# Schematic.net
KiCad netlist of a schematic drawn in EAGLE
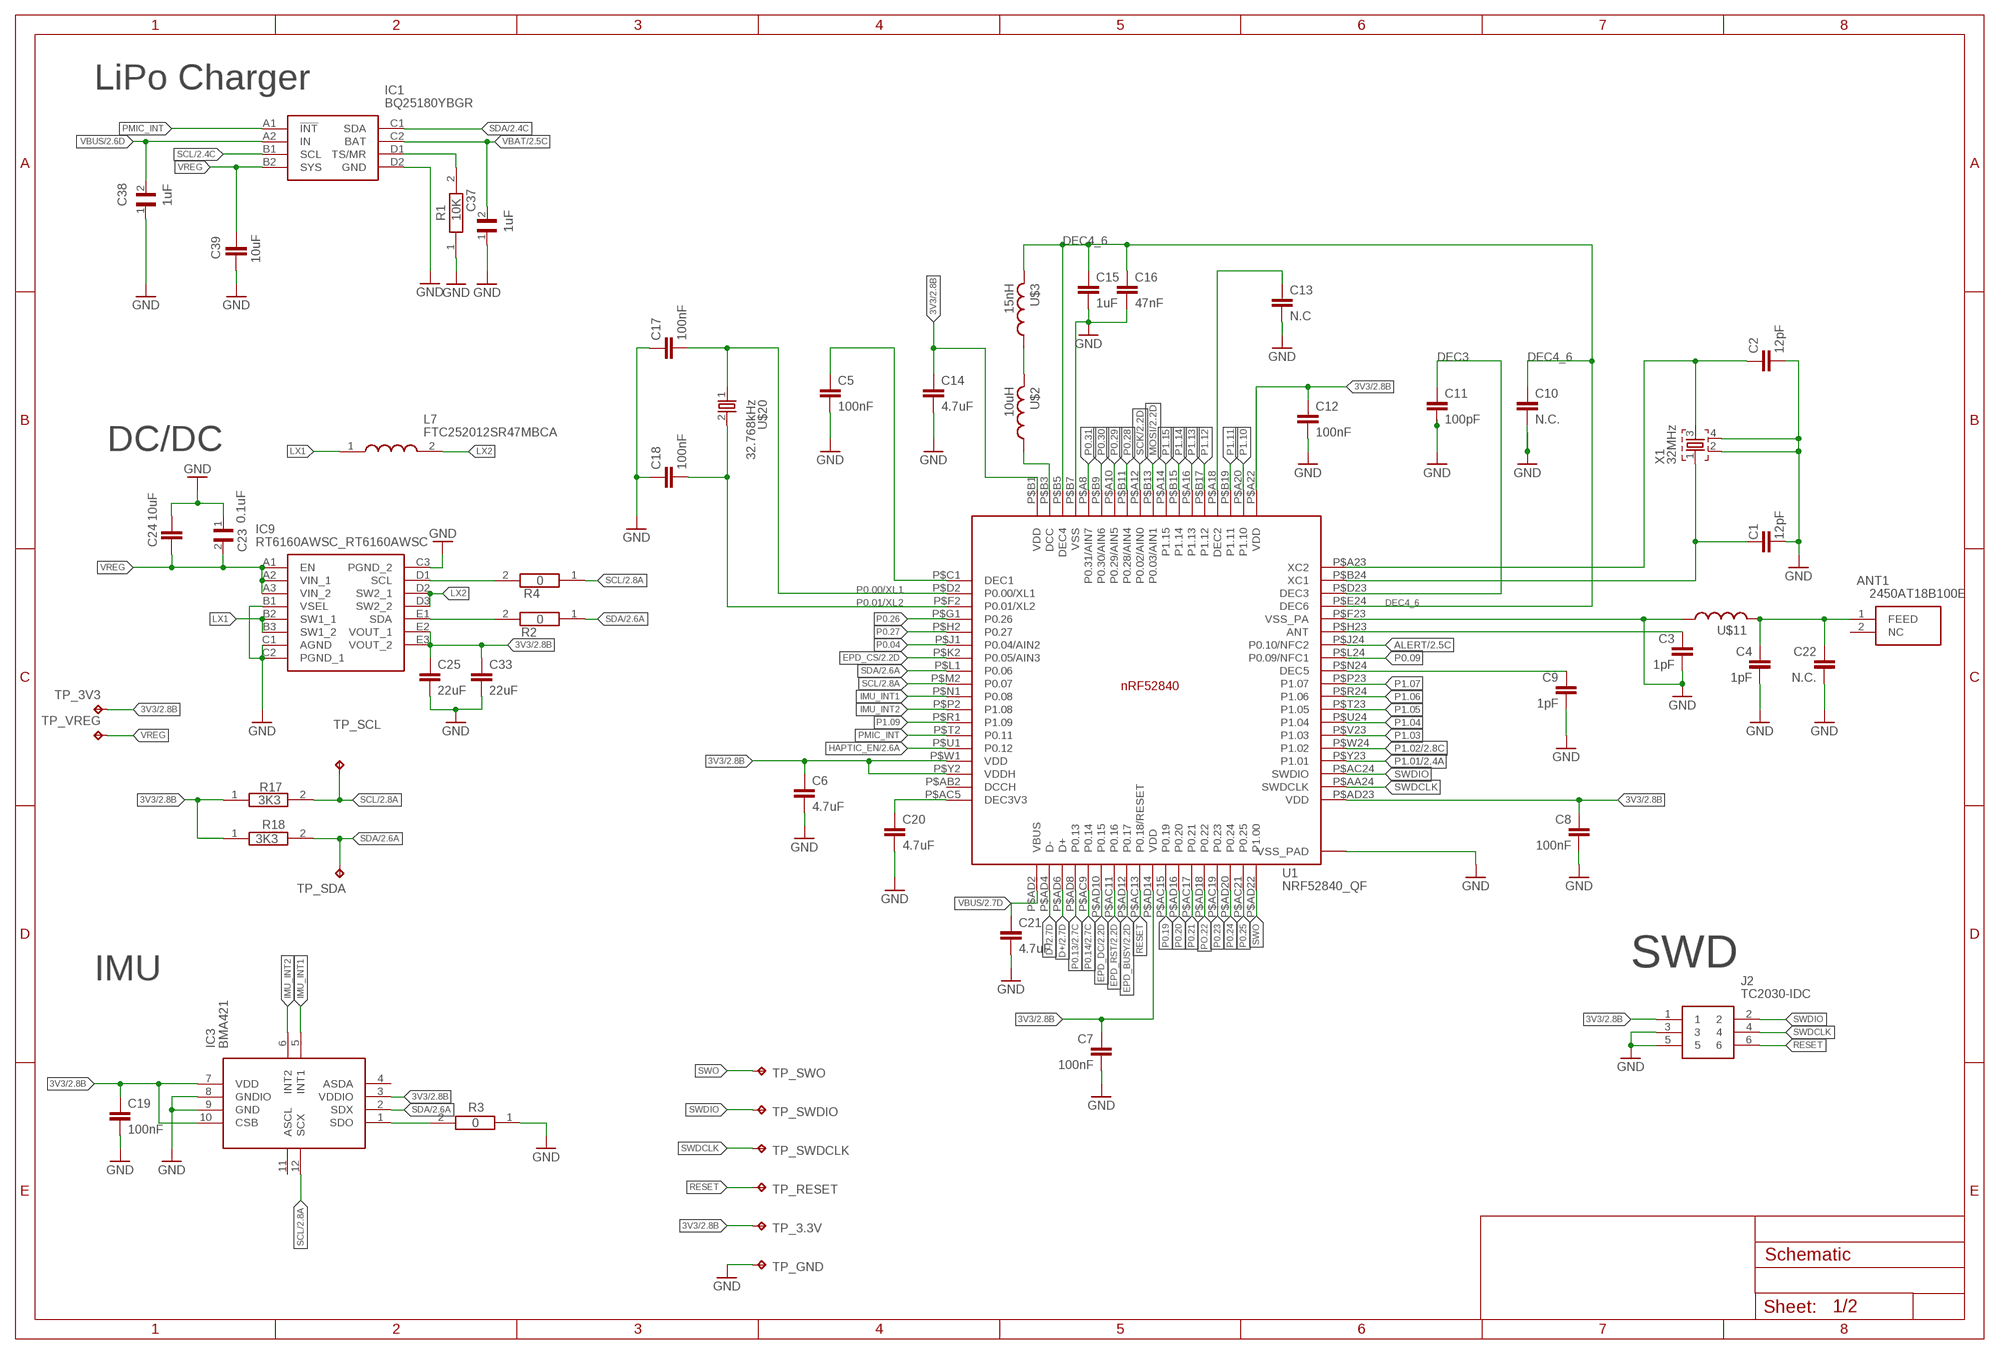
[diagram p0: schematic, sheet 1]
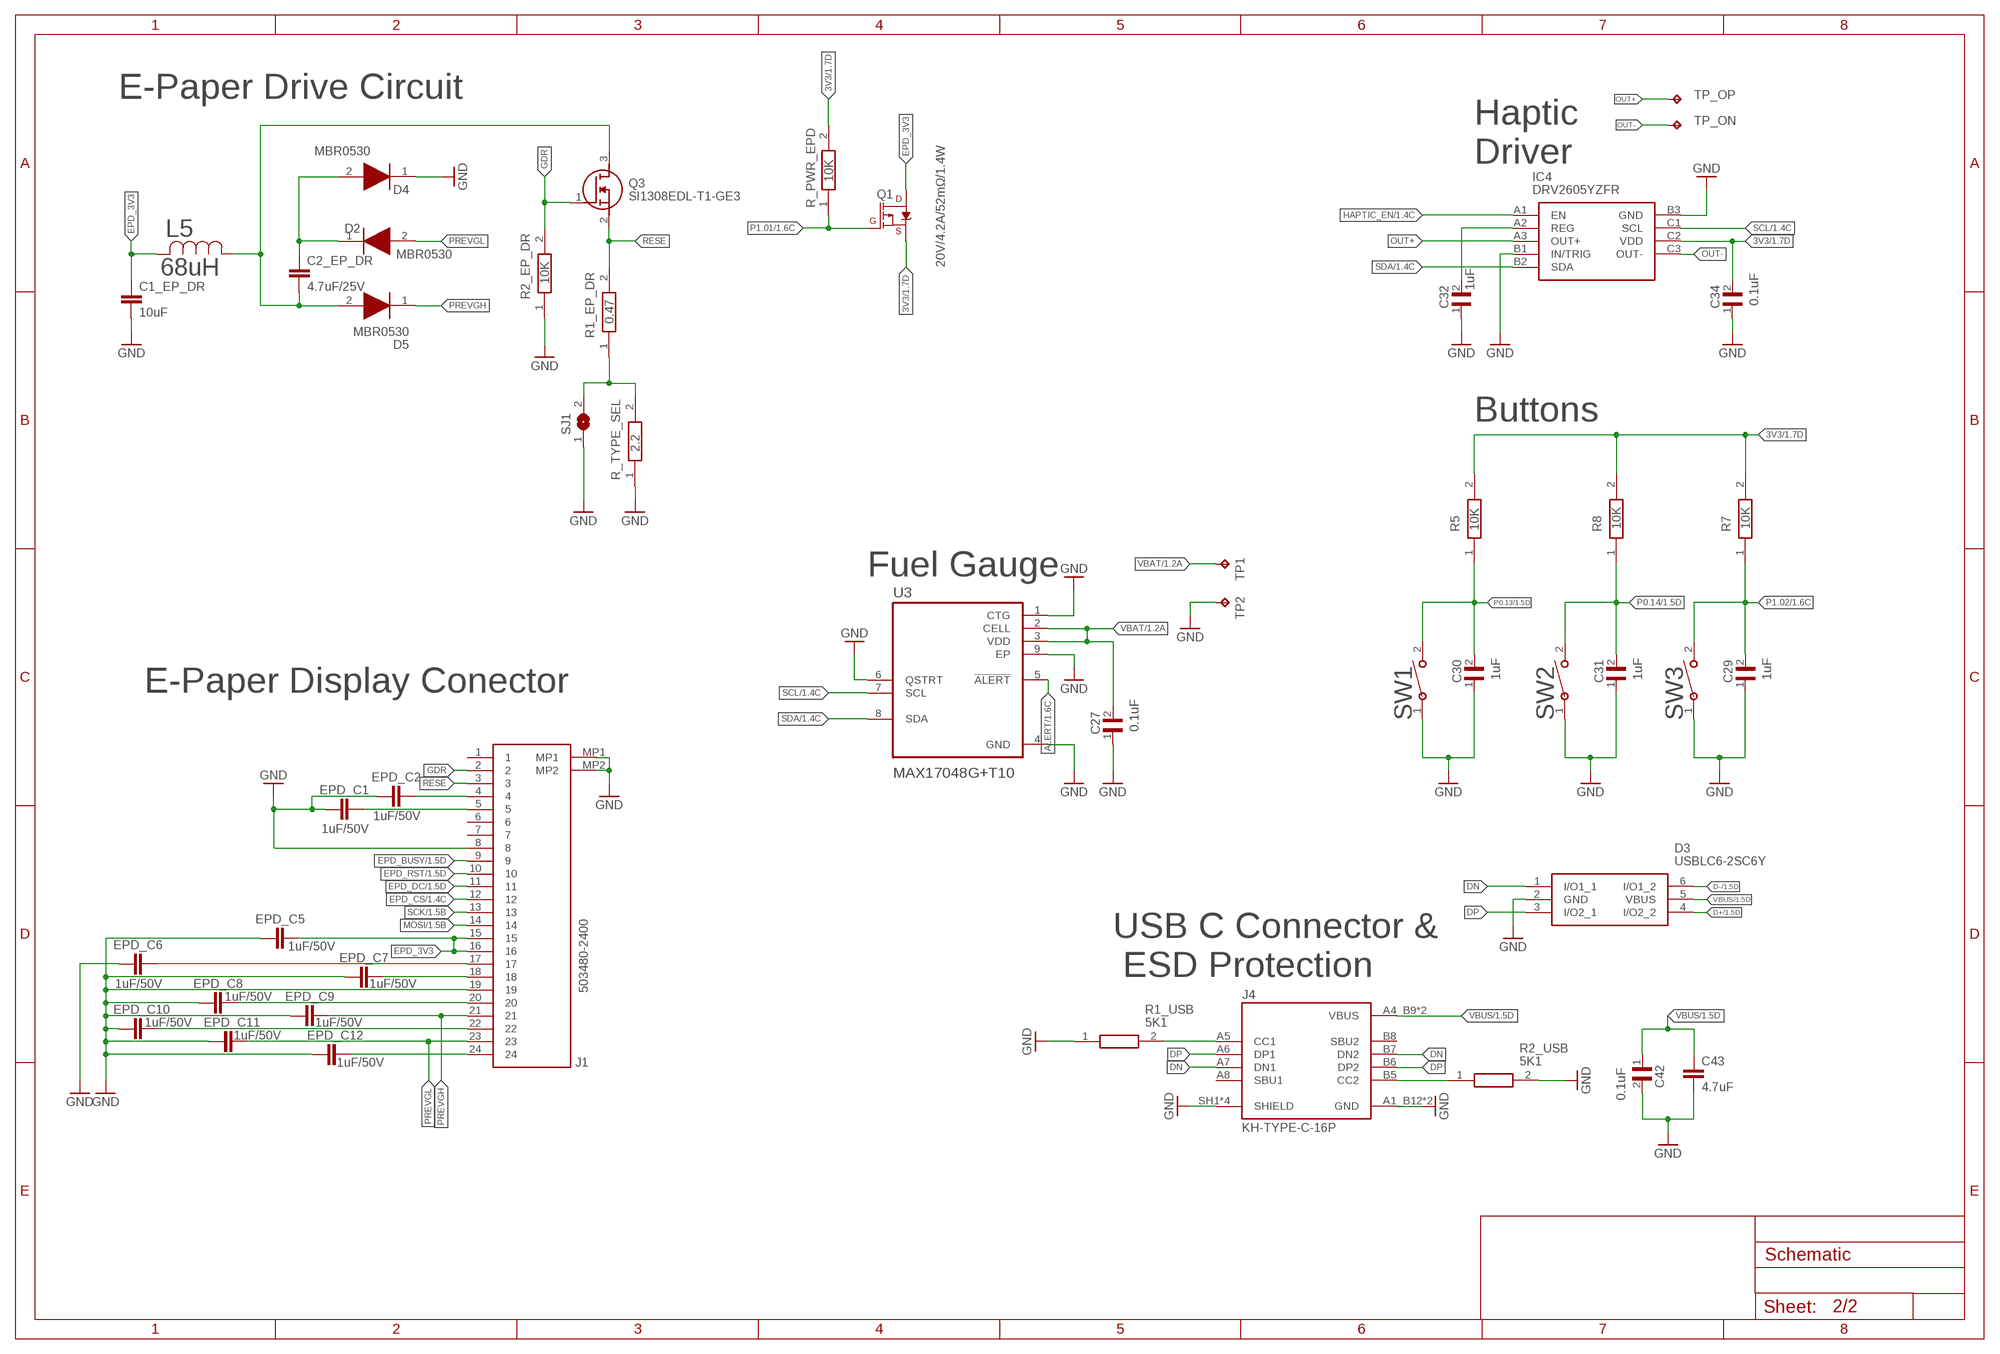
[diagram p1: schematic, sheet 2]

(export (version "E")
  (design (tool "Eeschema 10.0.6"))
  (components
    (comp (ref "C1_EP_DR")
      (value "10uF")
      (footprint "eagle-import:PERFECT_0402_0402")
      (libsource (lib "eagle-import") (part "PERFECT_0402_CAP_0402"))
    )
    (comp (ref "C2_EP_DR")
      (value "4.7uF/25V")
      (footprint "eagle-import:PERFECT_0402_0402")
      (libsource (lib "eagle-import") (part "PERFECT_0402_CAP_0402"))
    )
    (comp (ref "C27")
      (value "0.1uF")
      (footprint "eagle-import:GRM011R60J152KE01L_2_CAPC0201X13N")
      (fields (field (name "MF") "Murata") (field (name "MP") "GRM011R60J152KE01L"))
      (libsource (lib "eagle-import") (part "GRM011R60J152KE01L_2_GRM011R60J152KE01L"))
    )
    (comp (ref "C29")
      (value "1uF")
      (footprint "eagle-import:GRM011R60J152KE01L_2_CAPC0201X13N")
      (fields (field (name "MF") "Murata") (field (name "MP") "GRM011R60J152KE01L"))
      (libsource (lib "eagle-import") (part "GRM011R60J152KE01L_2_GRM011R60J152KE01L"))
    )
    (comp (ref "C30")
      (value "1uF")
      (footprint "eagle-import:GRM011R60J152KE01L_2_CAPC0201X13N")
      (fields (field (name "MF") "Murata") (field (name "MP") "GRM011R60J152KE01L"))
      (libsource (lib "eagle-import") (part "GRM011R60J152KE01L_2_GRM011R60J152KE01L"))
    )
    (comp (ref "C31")
      (value "1uF")
      (footprint "eagle-import:GRM011R60J152KE01L_2_CAPC0201X13N")
      (fields (field (name "MF") "Murata") (field (name "MP") "GRM011R60J152KE01L"))
      (libsource (lib "eagle-import") (part "GRM011R60J152KE01L_2_GRM011R60J152KE01L"))
    )
    (comp (ref "C32")
      (value "1uF")
      (footprint "eagle-import:GRM011R60J152KE01L_2_CAPC0201X13N")
      (fields (field (name "MF") "Murata") (field (name "MP") "GRM011R60J152KE01L"))
      (libsource (lib "eagle-import") (part "GRM011R60J152KE01L_2_GRM011R60J152KE01L"))
    )
    (comp (ref "C34")
      (value "0.1uF")
      (footprint "eagle-import:GRM011R60J152KE01L_2_CAPC0201X13N")
      (fields (field (name "MF") "Murata") (field (name "MP") "GRM011R60J152KE01L"))
      (libsource (lib "eagle-import") (part "GRM011R60J152KE01L_2_GRM011R60J152KE01L"))
    )
    (comp (ref "C42")
      (value "0.1uF")
      (footprint "eagle-import:GRM011R60J152KE01L_2_CAPC0201X13N")
      (fields (field (name "MF") "Murata") (field (name "MP") "GRM011R60J152KE01L"))
      (libsource (lib "eagle-import") (part "GRM011R60J152KE01L_2_GRM011R60J152KE01L"))
    )
    (comp (ref "C43")
      (value "4.7uF")
      (footprint "eagle-import:PERFECT_0402_0402")
      (libsource (lib "eagle-import") (part "PERFECT_0402_CAP_0402"))
    )
    (comp (ref "D2")
      (value "MBR0530")
      (footprint "eagle-import:ESP32_C6_LIBRARY_5_SOD3716X135N")
      (fields (field (name "MF") "ON Semiconductor"))
      (libsource (lib "eagle-import") (part "ESP32_C6_LIBRARY_5_MBR0530"))
    )
    (comp (ref "D3")
      (value "USBLC6-2SC6Y")
      (footprint "eagle-import:ESP32_C6_LIBRARY_3_SOT95P280X145-6N")
      (fields (field (name "MF") "STMicroelectronics"))
      (libsource (lib "eagle-import") (part "ESP32_C6_LIBRARY_3_USBLC6-2SC6Y"))
    )
    (comp (ref "D4")
      (value "MBR0530")
      (footprint "eagle-import:ESP32_C6_LIBRARY_5_SOD3716X135N")
      (fields (field (name "MF") "ON Semiconductor"))
      (libsource (lib "eagle-import") (part "ESP32_C6_LIBRARY_5_MBR0530"))
    )
    (comp (ref "D5")
      (value "MBR0530")
      (footprint "eagle-import:ESP32_C6_LIBRARY_5_SOD3716X135N")
      (fields (field (name "MF") "ON Semiconductor"))
      (libsource (lib "eagle-import") (part "ESP32_C6_LIBRARY_5_MBR0530"))
    )
    (comp (ref "EPD_C1")
      (value "1uF/50V")
      (footprint "eagle-import:PERFECT_0402_0402")
      (libsource (lib "eagle-import") (part "PERFECT_0402_CAP_0402"))
    )
    (comp (ref "EPD_C2")
      (value "1uF/50V")
      (footprint "eagle-import:PERFECT_0402_0402")
      (libsource (lib "eagle-import") (part "PERFECT_0402_CAP_0402"))
    )
    (comp (ref "EPD_C5")
      (value "1uF/50V")
      (footprint "eagle-import:PERFECT_0402_0402")
      (libsource (lib "eagle-import") (part "PERFECT_0402_CAP_0402"))
    )
    (comp (ref "EPD_C6")
      (value "1uF/50V")
      (footprint "eagle-import:PERFECT_0402_0402")
      (libsource (lib "eagle-import") (part "PERFECT_0402_CAP_0402"))
    )
    (comp (ref "EPD_C7")
      (value "1uF/50V")
      (footprint "eagle-import:PERFECT_0402_0402")
      (libsource (lib "eagle-import") (part "PERFECT_0402_CAP_0402"))
    )
    (comp (ref "EPD_C8")
      (value "1uF/50V")
      (footprint "eagle-import:PERFECT_0402_0402")
      (libsource (lib "eagle-import") (part "PERFECT_0402_CAP_0402"))
    )
    (comp (ref "EPD_C9")
      (value "1uF/50V")
      (footprint "eagle-import:PERFECT_0402_0402")
      (libsource (lib "eagle-import") (part "PERFECT_0402_CAP_0402"))
    )
    (comp (ref "EPD_C10")
      (value "1uF/50V")
      (footprint "eagle-import:PERFECT_0402_0402")
      (libsource (lib "eagle-import") (part "PERFECT_0402_CAP_0402"))
    )
    (comp (ref "EPD_C11")
      (value "1uF/50V")
      (footprint "eagle-import:PERFECT_0402_0402")
      (libsource (lib "eagle-import") (part "PERFECT_0402_CAP_0402"))
    )
    (comp (ref "EPD_C12")
      (value "1uF/50V")
      (footprint "eagle-import:PERFECT_0402_0402")
      (libsource (lib "eagle-import") (part "PERFECT_0402_CAP_0402"))
    )
    (comp (ref "IC4")
      (value "DRV2605YZFR")
      (footprint "eagle-import:DRV2605YZFR_BGA9C50P3X3_144X144X62")
      (libsource (lib "eagle-import") (part "DRV2605YZFR_DRV2605YZFR"))
    )
    (comp (ref "J1")
      (value "503480-2400")
      (footprint "eagle-import:503480-2400_5034802400")
      (fields (field (name "MOUSER_PART_NUMBER") "538-503480-2400"))
      (libsource (lib "eagle-import") (part "503480-2400_503480-2400"))
    )
    (comp (ref "J4")
      (value "KH-TYPE-C-16P")
      (footprint "eagle-import:KH-TYPE-C-16P_KINGHELM_KH-TYPE-C-16P")
      (fields (field (name "MF") "kinghelm"))
      (libsource (lib "eagle-import") (part "KH-TYPE-C-16P_KH-TYPE-C-16P"))
    )
    (comp (ref "L5")
      (value "68uH")
      (footprint "eagle-import:ESP32_C6_LIBRARY_2_IND_4828-WE-TPC_WRE")
      (fields
        (field (name "MANUFACTURER_PART_NUMBER") "744043680")
        (field (name "COPYRIGHT") "Copyright (C) 2024 Ultra Librarian. All rights reserved.")
      )
      (libsource (lib "eagle-import") (part "ESP32_C6_LIBRARY_2_744043680IND_4828-WE-TPC_WRE"))
    )
    (comp (ref "Q1")
      (value "20V/4.2A/52mΩ/1.4W")
      (footprint "eagle-import:ESP32_C6_LIBRARY_4_ESP32_C6_LIBRARY_4_ESP32_C6_LIBRARY_4_ESP32_C6_LIBRARY_4_ESP32_WROVER_SPARKFUN-DISCRETESEMI_SOT23-3")
      (libsource (lib "eagle-import") (part "ESP32_C6_LIBRARY_4_ESP32_WROVER_SPARKFUN-DISCRETESEMI_MOSFET_PCH-DMG2305UX-7"))
    )
    (comp (ref "Q3")
      (value "SI1308EDL-T1-GE3")
      (footprint "eagle-import:ESP32_C6_LIBRARY_6_SOT65P210X110-3N")
      (fields (field (name "MF") "Vishay Siliconix"))
      (libsource (lib "eagle-import") (part "ESP32_C6_LIBRARY_6_SI1308EDL-T1-GE3"))
    )
    (comp (ref "R1_EP_DR")
      (value "0.47")
      (footprint "eagle-import:CPF0201D7K68C1_0201")
      (libsource (lib "eagle-import") (part "CPF0201D7K68C1_CPF0201D7K68C1"))
    )
    (comp (ref "R1_USB")
      (value "5K1")
      (footprint "eagle-import:CPF0201D7K68C1_0201")
      (libsource (lib "eagle-import") (part "CPF0201D7K68C1_CPF0201D7K68C1"))
    )
    (comp (ref "R2_EP_DR")
      (value "10K")
      (footprint "eagle-import:CPF0201D7K68C1_0201")
      (libsource (lib "eagle-import") (part "CPF0201D7K68C1_CPF0201D7K68C1"))
    )
    (comp (ref "R2_USB")
      (value "5K1")
      (footprint "eagle-import:CPF0201D7K68C1_0201")
      (libsource (lib "eagle-import") (part "CPF0201D7K68C1_CPF0201D7K68C1"))
    )
    (comp (ref "R5")
      (value "10K")
      (footprint "eagle-import:CPF0201D7K68C1_0201")
      (libsource (lib "eagle-import") (part "CPF0201D7K68C1_CPF0201D7K68C1"))
    )
    (comp (ref "R7")
      (value "10K")
      (footprint "eagle-import:CPF0201D7K68C1_0201")
      (libsource (lib "eagle-import") (part "CPF0201D7K68C1_CPF0201D7K68C1"))
    )
    (comp (ref "R8")
      (value "10K")
      (footprint "eagle-import:CPF0201D7K68C1_0201")
      (libsource (lib "eagle-import") (part "CPF0201D7K68C1_CPF0201D7K68C1"))
    )
    (comp (ref "R_PWR_EPD")
      (value "10K")
      (footprint "eagle-import:CPF0201D7K68C1_0201")
      (libsource (lib "eagle-import") (part "CPF0201D7K68C1_CPF0201D7K68C1"))
    )
    (comp (ref "R_TYPE_SEL")
      (value "2.2")
      (footprint "eagle-import:CPF0201D7K68C1_0201")
      (libsource (lib "eagle-import") (part "CPF0201D7K68C1_CPF0201D7K68C1"))
    )
    (comp (ref "SJ1")
      (value "ESP32_C6_LIBRARY_7_JUMPER_SJ")
      (footprint "eagle-import:ESP32_C6_LIBRARY_7_JUMPER_SJ")
      (libsource (lib "eagle-import") (part "ESP32_C6_LIBRARY_7_JUMPER_SJ"))
    )
    (comp (ref "SW1")
      (value "2025-10-22_07-23-44_LIBRARY_EVP-AKE31ASW_EVP-AKE31A_PAN")
      (footprint "eagle-import:2025-10-22_07-23-44_LIBRARY_SW_EVP-AKE31A_PAN")
      (fields
        (field (name "MANUFACTURER_PART_NUMBER") "EVP-AKE31A")
        (field (name "COPYRIGHT") "Copyright (C) 2025 Ultra Librarian. All rights reserved.")
      )
      (libsource (lib "eagle-import") (part "2025-10-22_07-23-44_LIBRARY_EVP-AKE31ASW_EVP-AKE31A_PAN"))
    )
    (comp (ref "SW2")
      (value "2025-10-22_07-23-44_LIBRARY_EVP-AKE31ASW_EVP-AKE31A_PAN")
      (footprint "eagle-import:2025-10-22_07-23-44_LIBRARY_SW_EVP-AKE31A_PAN")
      (fields
        (field (name "MANUFACTURER_PART_NUMBER") "EVP-AKE31A")
        (field (name "COPYRIGHT") "Copyright (C) 2025 Ultra Librarian. All rights reserved.")
      )
      (libsource (lib "eagle-import") (part "2025-10-22_07-23-44_LIBRARY_EVP-AKE31ASW_EVP-AKE31A_PAN"))
    )
    (comp (ref "SW3")
      (value "2025-10-22_07-23-44_LIBRARY_EVP-AKE31ASW_EVP-AKE31A_PAN")
      (footprint "eagle-import:2025-10-22_07-23-44_LIBRARY_SW_EVP-AKE31A_PAN")
      (fields
        (field (name "MANUFACTURER_PART_NUMBER") "EVP-AKE31A")
        (field (name "COPYRIGHT") "Copyright (C) 2025 Ultra Librarian. All rights reserved.")
      )
      (libsource (lib "eagle-import") (part "2025-10-22_07-23-44_LIBRARY_EVP-AKE31ASW_EVP-AKE31A_PAN"))
    )
    (comp (ref "TP1")
      (value "HECTOR_WATCH_1_TPTP20R")
      (footprint "eagle-import:HECTOR_WATCH_1_TP20R")
      (libsource (lib "eagle-import") (part "HECTOR_WATCH_1_TPTP20R"))
    )
    (comp (ref "TP2")
      (value "HECTOR_WATCH_1_TPTP20R")
      (footprint "eagle-import:HECTOR_WATCH_1_TP20R")
      (libsource (lib "eagle-import") (part "HECTOR_WATCH_1_TPTP20R"))
    )
    (comp (ref "TP_ON")
      (value "HECTOR_WATCH_1_TPTP20R")
      (footprint "eagle-import:HECTOR_WATCH_1_TP20R")
      (libsource (lib "eagle-import") (part "HECTOR_WATCH_1_TPTP20R"))
    )
    (comp (ref "TP_OP")
      (value "HECTOR_WATCH_1_TPTP20R")
      (footprint "eagle-import:HECTOR_WATCH_1_TP20R")
      (libsource (lib "eagle-import") (part "HECTOR_WATCH_1_TPTP20R"))
    )
    (comp (ref "U3")
      (value "MAX17048G+T10")
      (footprint "eagle-import:ESP32_C6_LIBRARY_SON50P200X200X80-9N")
      (fields (field (name "MF") "Analog Devices"))
      (libsource (lib "eagle-import") (part "ESP32_C6_LIBRARY_MAX17048G+T10"))
    )
    (comp (ref "ANT1")
      (value "2450AT18B100E")
      (footprint "eagle-import:2450AT18B100E_ANTC3216X140N")
      (fields (field (name "MOUSER_PART_NUMBER") "609-2450AT18B100E"))
      (libsource (lib "eagle-import") (part "2450AT18B100E_2450AT18B100E"))
    )
    (comp (ref "C1")
      (value "12pF")
      (footprint "eagle-import:NORDIC_NRF_3_RESC0201_L")
      (libsource (lib "eagle-import") (part "NORDIC_NRF_3_CAPACITOR_0201_L"))
    )
    (comp (ref "C2")
      (value "12pF")
      (footprint "eagle-import:NORDIC_NRF_3_RESC0201_L")
      (libsource (lib "eagle-import") (part "NORDIC_NRF_3_CAPACITOR_0201_L"))
    )
    (comp (ref "C3")
      (value "1pF")
      (footprint "eagle-import:NORDIC_NRF_3_RESC0201_L")
      (libsource (lib "eagle-import") (part "NORDIC_NRF_3_CAPACITOR_0201_L"))
    )
    (comp (ref "C4")
      (value "1pF")
      (footprint "eagle-import:NORDIC_NRF_3_RESC0201_L")
      (libsource (lib "eagle-import") (part "NORDIC_NRF_3_CAPACITOR_0201_L"))
    )
    (comp (ref "C5")
      (value "100nF")
      (footprint "eagle-import:NORDIC_NRF_3_RESC0201_L")
      (libsource (lib "eagle-import") (part "NORDIC_NRF_3_CAPACITOR_0201_L"))
    )
    (comp (ref "C6")
      (value "4.7uF")
      (footprint "eagle-import:PERFECT_0402_0402")
      (libsource (lib "eagle-import") (part "PERFECT_0402_CAP_0402"))
    )
    (comp (ref "C7")
      (value "100nF")
      (footprint "eagle-import:NORDIC_NRF_3_RESC0201_L")
      (libsource (lib "eagle-import") (part "NORDIC_NRF_3_CAPACITOR_0201_L"))
    )
    (comp (ref "C8")
      (value "100nF")
      (footprint "eagle-import:NORDIC_NRF_3_RESC0201_L")
      (libsource (lib "eagle-import") (part "NORDIC_NRF_3_CAPACITOR_0201_L"))
    )
    (comp (ref "C9")
      (value "1pF")
      (footprint "eagle-import:NORDIC_NRF_3_RESC0201_L")
      (libsource (lib "eagle-import") (part "NORDIC_NRF_3_CAPACITOR_0201_L"))
    )
    (comp (ref "C10")
      (value "N.C.")
      (footprint "eagle-import:NORDIC_NRF_3_RESC0201_L")
      (libsource (lib "eagle-import") (part "NORDIC_NRF_3_CAPACITOR_0201_L"))
    )
    (comp (ref "C11")
      (value "100pF")
      (footprint "eagle-import:NORDIC_NRF_3_RESC0201_L")
      (libsource (lib "eagle-import") (part "NORDIC_NRF_3_CAPACITOR_0201_L"))
    )
    (comp (ref "C12")
      (value "100nF")
      (footprint "eagle-import:NORDIC_NRF_3_RESC0201_L")
      (libsource (lib "eagle-import") (part "NORDIC_NRF_3_CAPACITOR_0201_L"))
    )
    (comp (ref "C13")
      (value "N.C")
      (footprint "eagle-import:NORDIC_NRF_3_RESC0201_L")
      (libsource (lib "eagle-import") (part "NORDIC_NRF_3_CAPACITOR_0201_L"))
    )
    (comp (ref "C14")
      (value "4.7uF")
      (footprint "eagle-import:PERFECT_0402_0402")
      (libsource (lib "eagle-import") (part "PERFECT_0402_CAP_0402"))
    )
    (comp (ref "C15")
      (value "1uF")
      (footprint "eagle-import:PERFECT_0402_0402")
      (libsource (lib "eagle-import") (part "PERFECT_0402_CAP_0402"))
    )
    (comp (ref "C16")
      (value "47nF")
      (footprint "eagle-import:NORDIC_NRF_3_RESC0201_L")
      (libsource (lib "eagle-import") (part "NORDIC_NRF_3_CAPACITOR_0201_L"))
    )
    (comp (ref "C17")
      (value "100nF")
      (footprint "eagle-import:NORDIC_NRF_3_RESC0201_L")
      (libsource (lib "eagle-import") (part "NORDIC_NRF_3_CAPACITOR_0201_L"))
    )
    (comp (ref "C18")
      (value "100nF")
      (footprint "eagle-import:NORDIC_NRF_3_RESC0201_L")
      (libsource (lib "eagle-import") (part "NORDIC_NRF_3_CAPACITOR_0201_L"))
    )
    (comp (ref "C19")
      (value "100nF")
      (footprint "eagle-import:NORDIC_NRF_3_RESC0201_L")
      (libsource (lib "eagle-import") (part "NORDIC_NRF_3_CAPACITOR_0201_L"))
    )
    (comp (ref "C20")
      (value "4.7uF")
      (footprint "eagle-import:PERFECT_0402_0402")
      (libsource (lib "eagle-import") (part "PERFECT_0402_CAP_0402"))
    )
    (comp (ref "C21")
      (value "4.7uF")
      (footprint "eagle-import:PERFECT_0402_0402")
      (libsource (lib "eagle-import") (part "PERFECT_0402_CAP_0402"))
    )
    (comp (ref "C22")
      (value "N.C.")
      (footprint "eagle-import:NORDIC_NRF_3_RESC0201_L")
      (libsource (lib "eagle-import") (part "NORDIC_NRF_3_CAPACITOR_0201_L"))
    )
    (comp (ref "C23")
      (value "0.1uF")
      (footprint "eagle-import:GRM011R60J152KE01L_2_CAPC0201X13N")
      (fields (field (name "MF") "Murata") (field (name "MP") "GRM011R60J152KE01L"))
      (libsource (lib "eagle-import") (part "GRM011R60J152KE01L_2_GRM011R60J152KE01L"))
    )
    (comp (ref "C24")
      (value "10uF")
      (footprint "eagle-import:PERFECT_0402_0402")
      (libsource (lib "eagle-import") (part "PERFECT_0402_CAP_0402"))
    )
    (comp (ref "C25")
      (value "22uF")
      (footprint "eagle-import:PERFECT_0402_0402")
      (libsource (lib "eagle-import") (part "PERFECT_0402_CAP_0402"))
    )
    (comp (ref "C33")
      (value "22uF")
      (footprint "eagle-import:PERFECT_0402_0402")
      (libsource (lib "eagle-import") (part "PERFECT_0402_CAP_0402"))
    )
    (comp (ref "C37")
      (value "1uF")
      (footprint "eagle-import:GRM011R60J152KE01L_1_0201")
      (libsource (lib "eagle-import") (part "GRM011R60J152KE01L_1_GRM011R60J152KE01L"))
    )
    (comp (ref "C38")
      (value "1uF")
      (footprint "eagle-import:GRM011R60J152KE01L_1_0201")
      (libsource (lib "eagle-import") (part "GRM011R60J152KE01L_1_GRM011R60J152KE01L"))
    )
    (comp (ref "C39")
      (value "10uF")
      (footprint "eagle-import:PERFECT_0402_0402")
      (libsource (lib "eagle-import") (part "PERFECT_0402_CAP_0402"))
    )
    (comp (ref "IC1")
      (value "BQ25180YBGR")
      (footprint "eagle-import:BQ25180YBGR_BGA8C40P2X4_100X155X50")
      (fields (field (name "MOUSER_PART_NUMBER") "595-BQ25180YBGR"))
      (libsource (lib "eagle-import") (part "BQ25180YBGR_BQ25180YBGR"))
    )
    (comp (ref "IC3")
      (value "BMA421")
      (footprint "eagle-import:BMA423_BMA423")
      (fields (field (name "ARROW_PART_NUMBER") "BMA423") (field (name "MOUSER_PART_NUMBER") "262-BMA423"))
      (libsource (lib "eagle-import") (part "BMA423_BMA423"))
    )
    (comp (ref "IC9")
      (value "RT6160AWSC_RT6160AWSC")
      (footprint "eagle-import:RT6160AWSC_BGA15C40P3X5_140X230X60")
      (fields
        (field (name "MANUFACTURER_PART_NUMBER") "RT6160AWSC")
        (field (name "MOUSER_PART_NUMBER") "835-RT6160AWSC")
      )
      (libsource (lib "eagle-import") (part "RT6160AWSC_RT6160AWSC"))
    )
    (comp (ref "J2")
      (value "TC2030-IDC")
      (footprint "eagle-import:TC2030-IDC_TC2030IDC")
      (libsource (lib "eagle-import") (part "TC2030-IDC_TC2030-IDC"))
    )
    (comp (ref "L7")
      (value "FTC252012SR47MBCA")
      (footprint "eagle-import:MLP2016SR47MT0S1_INDC2016X100N")
      (libsource (lib "eagle-import") (part "MLP2016SR47MT0S1_FTC252012SR47MBCA"))
    )
    (comp (ref "R1")
      (value "10K")
      (footprint "eagle-import:CPF0201D7K68C1_0201")
      (libsource (lib "eagle-import") (part "CPF0201D7K68C1_CPF0201D7K68C1"))
    )
    (comp (ref "R2")
      (value "0")
      (footprint "eagle-import:CPF0201D7K68C1_0201")
      (libsource (lib "eagle-import") (part "CPF0201D7K68C1_CPF0201D7K68C1"))
    )
    (comp (ref "R3")
      (value "0")
      (footprint "eagle-import:CPF0201D7K68C1_0201")
      (libsource (lib "eagle-import") (part "CPF0201D7K68C1_CPF0201D7K68C1"))
    )
    (comp (ref "R4")
      (value "0")
      (footprint "eagle-import:CPF0201D7K68C1_0201")
      (libsource (lib "eagle-import") (part "CPF0201D7K68C1_CPF0201D7K68C1"))
    )
    (comp (ref "R17")
      (value "3K3")
      (footprint "eagle-import:CPF0201D7K68C1_0201")
      (libsource (lib "eagle-import") (part "CPF0201D7K68C1_CPF0201D7K68C1"))
    )
    (comp (ref "R18")
      (value "3K3")
      (footprint "eagle-import:CPF0201D7K68C1_0201")
      (libsource (lib "eagle-import") (part "CPF0201D7K68C1_CPF0201D7K68C1"))
    )
    (comp (ref "TP_3.3V")
      (value "HECTOR_WATCH_1_TPTP20R")
      (footprint "eagle-import:HECTOR_WATCH_1_TP20R")
      (libsource (lib "eagle-import") (part "HECTOR_WATCH_1_TPTP20R"))
    )
    (comp (ref "TP_3V3")
      (value "HECTOR_WATCH_1_TPTP20R")
      (footprint "eagle-import:HECTOR_WATCH_1_TP20R")
      (libsource (lib "eagle-import") (part "HECTOR_WATCH_1_TPTP20R"))
    )
    (comp (ref "TP_GND")
      (value "HECTOR_WATCH_1_TPTP20R")
      (footprint "eagle-import:HECTOR_WATCH_1_TP20R")
      (libsource (lib "eagle-import") (part "HECTOR_WATCH_1_TPTP20R"))
    )
    (comp (ref "TP_RESET")
      (value "HECTOR_WATCH_1_TPTP20R")
      (footprint "eagle-import:HECTOR_WATCH_1_TP20R")
      (libsource (lib "eagle-import") (part "HECTOR_WATCH_1_TPTP20R"))
    )
    (comp (ref "TP_SCL")
      (value "HECTOR_WATCH_1_TPTP20R")
      (footprint "eagle-import:HECTOR_WATCH_1_TP20R")
      (libsource (lib "eagle-import") (part "HECTOR_WATCH_1_TPTP20R"))
    )
    (comp (ref "TP_SDA")
      (value "HECTOR_WATCH_1_TPTP20R")
      (footprint "eagle-import:HECTOR_WATCH_1_TP20R")
      (libsource (lib "eagle-import") (part "HECTOR_WATCH_1_TPTP20R"))
    )
    (comp (ref "TP_SWDCLK")
      (value "HECTOR_WATCH_1_TPTP20R")
      (footprint "eagle-import:HECTOR_WATCH_1_TP20R")
      (libsource (lib "eagle-import") (part "HECTOR_WATCH_1_TPTP20R"))
    )
    (comp (ref "TP_SWDIO")
      (value "HECTOR_WATCH_1_TPTP20R")
      (footprint "eagle-import:HECTOR_WATCH_1_TP20R")
      (libsource (lib "eagle-import") (part "HECTOR_WATCH_1_TPTP20R"))
    )
    (comp (ref "TP_SWO")
      (value "HECTOR_WATCH_1_TPTP20R")
      (footprint "eagle-import:HECTOR_WATCH_1_TP20R")
      (libsource (lib "eagle-import") (part "HECTOR_WATCH_1_TPTP20R"))
    )
    (comp (ref "TP_VREG")
      (value "HECTOR_WATCH_1_TPTP20R")
      (footprint "eagle-import:HECTOR_WATCH_1_TP20R")
      (libsource (lib "eagle-import") (part "HECTOR_WATCH_1_TPTP20R"))
    )
    (comp (ref "U$2")
      (value "10uH")
      (footprint "eagle-import:NORDIC_NRF_2_RESC0402_L")
      (libsource (lib "eagle-import") (part "NORDIC_NRF_2_INDUCTOR_0402_L"))
    )
    (comp (ref "U$3")
      (value "15nH")
      (footprint "eagle-import:NORDIC_NRF_2_RESC0402_L")
      (libsource (lib "eagle-import") (part "NORDIC_NRF_2_INDUCTOR_0402_L"))
    )
    (comp (ref "U$11")
      (value "NORDIC_NRF_2_INDUCTOR_0402_L")
      (footprint "eagle-import:NORDIC_NRF_2_RESC0402_L")
      (libsource (lib "eagle-import") (part "NORDIC_NRF_2_INDUCTOR_0402_L"))
    )
    (comp (ref "U$20")
      (value "32.768kHz")
      (footprint "eagle-import:NORDIC_NRF_1_XTAL_3215_N")
      (libsource (lib "eagle-import") (part "NORDIC_NRF_1_XTAL_32KHZ"))
    )
    (comp (ref "U1")
      (value "NRF52840_QF")
      (footprint "eagle-import:NORDIC_NRF_4_AQFN50P700X700X85_HS-74N")
      (libsource (lib "eagle-import") (part "NORDIC_NRF_4_NRF52840_QF"))
    )
    (comp (ref "X1")
      (value "32MHz")
      (footprint "eagle-import:NORDIC_NRF_BT-XTAL_2016_N")
      (libsource (lib "eagle-import") (part "NORDIC_NRF_XTAL_32MHZ"))
    )
  )
  (nets
    (net (code "1") (name "3V3") (class "Default")
      (node (ref "C12") (pin "1") (pinfunction "1_1") (pintype "passive"))
      (node (ref "C14") (pin "1") (pinfunction "1_1") (pintype "passive"))
      (node (ref "C19") (pin "1") (pinfunction "1_1") (pintype "passive"))
      (node (ref "C25") (pin "1") (pinfunction "1_1") (pintype "passive"))
      (node (ref "C33") (pin "1") (pinfunction "1_1") (pintype "passive"))
      (node (ref "C34") (pin "2") (pinfunction "2_2") (pintype "passive"))
      (node (ref "C6") (pin "1") (pinfunction "1_1") (pintype "passive"))
      (node (ref "C7") (pin "1") (pinfunction "1_1") (pintype "passive"))
      (node (ref "C8") (pin "1") (pinfunction "1_1") (pintype "passive"))
      (node (ref "IC3") (pin "10") (pinfunction "CSB_10") (pintype "bidirectional"))
      (node (ref "IC3") (pin "3") (pinfunction "VDDIO_3") (pintype "bidirectional"))
      (node (ref "IC3") (pin "7") (pinfunction "VDD_7") (pintype "bidirectional"))
      (node (ref "IC4") (pin "C2") (pinfunction "VDD_C2") (pintype "bidirectional"))
      (node (ref "IC9") (pin "E2") (pinfunction "VOUT_1_E2") (pintype "bidirectional"))
      (node (ref "IC9") (pin "E3") (pinfunction "VOUT_2_E3") (pintype "bidirectional"))
      (node (ref "J2") (pin "1") (pinfunction "1_1") (pintype "bidirectional"))
      (node (ref "Q1") (pin "2") (pinfunction "S_2") (pintype "bidirectional"))
      (node (ref "R17") (pin "1") (pinfunction "1_1") (pintype "bidirectional"))
      (node (ref "R18") (pin "1") (pinfunction "1_1") (pintype "bidirectional"))
      (node (ref "R5") (pin "2") (pinfunction "2_2") (pintype "bidirectional"))
      (node (ref "R7") (pin "2") (pinfunction "2_2") (pintype "bidirectional"))
      (node (ref "R8") (pin "2") (pinfunction "2_2") (pintype "bidirectional"))
      (node (ref "R_PWR_EPD") (pin "2") (pinfunction "2_2") (pintype "bidirectional"))
      (node (ref "TP_3.3V") (pin "TP") (pinfunction "TP_TP") (pintype "input"))
      (node (ref "TP_3V3") (pin "TP") (pinfunction "TP_TP") (pintype "input"))
      (node (ref "U1") (pin "P$A22") (pinfunction "VDD_P$A22") (pintype "power_in"))
      (node (ref "U1") (pin "P$AD14") (pinfunction "VDD_P$AD14") (pintype "power_in"))
      (node (ref "U1") (pin "P$AD23") (pinfunction "VDD_P$AD23") (pintype "power_in"))
      (node (ref "U1") (pin "P$B1") (pinfunction "VDD_P$B1") (pintype "power_in"))
      (node (ref "U1") (pin "P$W1") (pinfunction "VDD_P$W1") (pintype "power_in"))
      (node (ref "U1") (pin "P$Y2") (pinfunction "VDDH_P$Y2") (pintype "power_in"))
    )
    (net (code "2") (name "ALERT") (class "Default")
      (node (ref "U1") (pin "P$J24") (pinfunction "P0.10/NFC2_P$J24") (pintype "bidirectional"))
      (node (ref "U3") (pin "5") (pinfunction "~{ALERT}_5") (pintype "output"))
    )
    (net (code "3") (name "D+") (class "Default")
      (node (ref "D3") (pin "4") (pinfunction "I/O2_2_4") (pintype "bidirectional"))
      (node (ref "U1") (pin "P$AD6") (pinfunction "D+_P$AD6") (pintype "bidirectional"))
    )
    (net (code "4") (name "D-") (class "Default")
      (node (ref "D3") (pin "6") (pinfunction "I/O1_2_6") (pintype "bidirectional"))
      (node (ref "U1") (pin "P$AD4") (pinfunction "D-_P$AD4") (pintype "bidirectional"))
    )
    (net (code "5") (name "DEC3") (class "Default")
      (node (ref "C11") (pin "1") (pinfunction "1_1") (pintype "passive"))
      (node (ref "U1") (pin "P$D23") (pinfunction "DEC3_P$D23") (pintype "bidirectional"))
    )
    (net (code "6") (name "DEC4_6") (class "Default")
      (node (ref "C10") (pin "1") (pinfunction "1_1") (pintype "passive"))
      (node (ref "C15") (pin "1") (pinfunction "1_1") (pintype "passive"))
      (node (ref "C16") (pin "1") (pinfunction "1_1") (pintype "passive"))
      (node (ref "U$3") (pin "2") (pinfunction "2_2") (pintype "passive"))
      (node (ref "U1") (pin "P$B5") (pinfunction "DEC4_P$B5") (pintype "power_in"))
      (node (ref "U1") (pin "P$E24") (pinfunction "DEC6_P$E24") (pintype "bidirectional"))
    )
    (net (code "7") (name "DN") (class "Default")
      (node (ref "D3") (pin "1") (pinfunction "I/O1_1_1") (pintype "bidirectional"))
      (node (ref "J4") (pin "A7") (pinfunction "DN1_A7") (pintype "bidirectional"))
      (node (ref "J4") (pin "B7") (pinfunction "DN2_B7") (pintype "bidirectional"))
    )
    (net (code "8") (name "DP") (class "Default")
      (node (ref "D3") (pin "3") (pinfunction "I/O2_1_3") (pintype "bidirectional"))
      (node (ref "J4") (pin "A6") (pinfunction "DP1_A6") (pintype "bidirectional"))
      (node (ref "J4") (pin "B6") (pinfunction "DP2_B6") (pintype "bidirectional"))
    )
    (net (code "9") (name "EPD_3V3") (class "Default")
      (node (ref "C1_EP_DR") (pin "1") (pinfunction "1_1") (pintype "passive"))
      (node (ref "EPD_C5") (pin "2") (pinfunction "2_2") (pintype "passive"))
      (node (ref "J1") (pin "15") (pinfunction "15_15") (pintype "bidirectional"))
      (node (ref "J1") (pin "16") (pinfunction "16_16") (pintype "bidirectional"))
      (node (ref "L5") (pin "2") (pinfunction "2_2") (pintype "passive"))
      (node (ref "Q1") (pin "3") (pinfunction "D_3") (pintype "bidirectional"))
    )
    (net (code "10") (name "EPD_BUSY") (class "Default")
      (node (ref "J1") (pin "9") (pinfunction "9_9") (pintype "bidirectional"))
      (node (ref "U1") (pin "P$AD12") (pinfunction "P0.17_P$AD12") (pintype "bidirectional"))
    )
    (net (code "11") (name "EPD_CS") (class "Default")
      (node (ref "J1") (pin "12") (pinfunction "12_12") (pintype "bidirectional"))
      (node (ref "U1") (pin "P$K2") (pinfunction "P0.05/AIN3_P$K2") (pintype "bidirectional"))
    )
    (net (code "12") (name "EPD_DC") (class "Default")
      (node (ref "J1") (pin "11") (pinfunction "11_11") (pintype "bidirectional"))
      (node (ref "U1") (pin "P$AD10") (pinfunction "P0.15_P$AD10") (pintype "bidirectional"))
    )
    (net (code "13") (name "EPD_RST") (class "Default")
      (node (ref "J1") (pin "10") (pinfunction "10_10") (pintype "bidirectional"))
      (node (ref "U1") (pin "P$AC11") (pinfunction "P0.16_P$AC11") (pintype "bidirectional"))
    )
    (net (code "14") (name "GDR") (class "Default")
      (node (ref "J1") (pin "2") (pinfunction "2_2") (pintype "bidirectional"))
      (node (ref "Q3") (pin "1") (pinfunction "G_1") (pintype "bidirectional"))
      (node (ref "R2_EP_DR") (pin "2") (pinfunction "2_2") (pintype "bidirectional"))
    )
    (net (code "15") (name "GND") (class "Default")
      (node (ref "C1") (pin "2") (pinfunction "2_2") (pintype "passive"))
      (node (ref "C10") (pin "2") (pinfunction "2_2") (pintype "passive"))
      (node (ref "C11") (pin "2") (pinfunction "2_2") (pintype "passive"))
      (node (ref "C12") (pin "2") (pinfunction "2_2") (pintype "passive"))
      (node (ref "C13") (pin "2") (pinfunction "2_2") (pintype "passive"))
      (node (ref "C14") (pin "2") (pinfunction "2_2") (pintype "passive"))
      (node (ref "C15") (pin "2") (pinfunction "2_2") (pintype "passive"))
      (node (ref "C16") (pin "2") (pinfunction "2_2") (pintype "passive"))
      (node (ref "C17") (pin "1") (pinfunction "1_1") (pintype "passive"))
      (node (ref "C18") (pin "1") (pinfunction "1_1") (pintype "passive"))
      (node (ref "C19") (pin "2") (pinfunction "2_2") (pintype "passive"))
      (node (ref "C1_EP_DR") (pin "2") (pinfunction "2_2") (pintype "passive"))
      (node (ref "C2") (pin "2") (pinfunction "2_2") (pintype "passive"))
      (node (ref "C20") (pin "2") (pinfunction "2_2") (pintype "passive"))
      (node (ref "C21") (pin "2") (pinfunction "2_2") (pintype "passive"))
      (node (ref "C22") (pin "2") (pinfunction "2_2") (pintype "passive"))
      (node (ref "C23") (pin "1") (pinfunction "1_1") (pintype "passive"))
      (node (ref "C24") (pin "1") (pinfunction "1_1") (pintype "passive"))
      (node (ref "C25") (pin "2") (pinfunction "2_2") (pintype "passive"))
      (node (ref "C27") (pin "1") (pinfunction "1_1") (pintype "passive"))
      (node (ref "C29") (pin "1") (pinfunction "1_1") (pintype "passive"))
      (node (ref "C3") (pin "2") (pinfunction "2_2") (pintype "passive"))
      (node (ref "C30") (pin "1") (pinfunction "1_1") (pintype "passive"))
      (node (ref "C31") (pin "1") (pinfunction "1_1") (pintype "passive"))
      (node (ref "C32") (pin "1") (pinfunction "1_1") (pintype "passive"))
      (node (ref "C33") (pin "2") (pinfunction "2_2") (pintype "passive"))
      (node (ref "C34") (pin "1") (pinfunction "1_1") (pintype "passive"))
      (node (ref "C37") (pin "1") (pinfunction "1_1") (pintype "passive"))
      (node (ref "C38") (pin "1") (pinfunction "1_1") (pintype "passive"))
      (node (ref "C39") (pin "2") (pinfunction "2_2") (pintype "passive"))
      (node (ref "C4") (pin "2") (pinfunction "2_2") (pintype "passive"))
      (node (ref "C42") (pin "2") (pinfunction "2_2") (pintype "passive"))
      (node (ref "C43") (pin "2") (pinfunction "2_2") (pintype "passive"))
      (node (ref "C5") (pin "2") (pinfunction "2_2") (pintype "passive"))
      (node (ref "C6") (pin "2") (pinfunction "2_2") (pintype "passive"))
      (node (ref "C7") (pin "2") (pinfunction "2_2") (pintype "passive"))
      (node (ref "C8") (pin "2") (pinfunction "2_2") (pintype "passive"))
      (node (ref "C9") (pin "2") (pinfunction "2_2") (pintype "passive"))
      (node (ref "D3") (pin "2") (pinfunction "GND_2") (pintype "bidirectional"))
      (node (ref "D4") (pin "1") (pinfunction "K_1") (pintype "bidirectional"))
      (node (ref "EPD_C1") (pin "1") (pinfunction "1_1") (pintype "passive"))
      (node (ref "EPD_C10") (pin "1") (pinfunction "1_1") (pintype "passive"))
      (node (ref "EPD_C11") (pin "1") (pinfunction "1_1") (pintype "passive"))
      (node (ref "EPD_C12") (pin "1") (pinfunction "1_1") (pintype "passive"))
      (node (ref "EPD_C2") (pin "1") (pinfunction "1_1") (pintype "passive"))
      (node (ref "EPD_C5") (pin "1") (pinfunction "1_1") (pintype "passive"))
      (node (ref "EPD_C6") (pin "1") (pinfunction "1_1") (pintype "passive"))
      (node (ref "EPD_C7") (pin "1") (pinfunction "1_1") (pintype "passive"))
      (node (ref "EPD_C8") (pin "1") (pinfunction "1_1") (pintype "passive"))
      (node (ref "EPD_C9") (pin "1") (pinfunction "1_1") (pintype "passive"))
      (node (ref "IC1") (pin "D2") (pinfunction "GND_D2") (pintype "bidirectional"))
      (node (ref "IC3") (pin "8") (pinfunction "GNDIO_8") (pintype "bidirectional"))
      (node (ref "IC3") (pin "9") (pinfunction "GND_9") (pintype "bidirectional"))
      (node (ref "IC4") (pin "B1") (pinfunction "IN/TRIG_B1") (pintype "bidirectional"))
      (node (ref "IC4") (pin "B3") (pinfunction "GND_B3") (pintype "bidirectional"))
      (node (ref "IC9") (pin "B1") (pinfunction "VSEL_B1") (pintype "bidirectional"))
      (node (ref "IC9") (pin "C1") (pinfunction "AGND_C1") (pintype "bidirectional"))
      (node (ref "IC9") (pin "C2") (pinfunction "PGND_1_C2") (pintype "bidirectional"))
      (node (ref "IC9") (pin "C3") (pinfunction "PGND_2_C3") (pintype "bidirectional"))
      (node (ref "J1") (pin "19") (pinfunction "19_19") (pintype "bidirectional"))
      (node (ref "J1") (pin "8") (pinfunction "8_8") (pintype "bidirectional"))
      (node (ref "J1") (pin "MP1") (pinfunction "MP1_MP1") (pintype "bidirectional"))
      (node (ref "J1") (pin "MP2") (pinfunction "MP2_MP2") (pintype "bidirectional"))
      (node (ref "J2") (pin "3") (pinfunction "3_3") (pintype "bidirectional"))
      (node (ref "J2") (pin "5") (pinfunction "5_5") (pintype "bidirectional"))
      (node (ref "J4") (pin "A12_B1") (pinfunction "GND_A12_B1") (pintype "power_in"))
      (node (ref "J4") (pin "A1_B12") (pinfunction "GND_A1_B12") (pintype "power_in"))
      (node (ref "J4") (pin "SH1") (pinfunction "SHIELD_SH1") (pintype "passive"))
      (node (ref "J4") (pin "SH2") (pinfunction "SHIELD_SH2") (pintype "passive"))
      (node (ref "J4") (pin "SH3") (pinfunction "SHIELD_SH3") (pintype "passive"))
      (node (ref "J4") (pin "SH4") (pinfunction "SHIELD_SH4") (pintype "passive"))
      (node (ref "R1") (pin "1") (pinfunction "1_1") (pintype "bidirectional"))
      (node (ref "R1_USB") (pin "1") (pinfunction "1_1") (pintype "bidirectional"))
      (node (ref "R2_EP_DR") (pin "1") (pinfunction "1_1") (pintype "bidirectional"))
      (node (ref "R2_USB") (pin "2") (pinfunction "2_2") (pintype "bidirectional"))
      (node (ref "R3") (pin "1") (pinfunction "1_1") (pintype "bidirectional"))
      (node (ref "R_TYPE_SEL") (pin "1") (pinfunction "1_1") (pintype "bidirectional"))
      (node (ref "SJ1") (pin "1") (pinfunction "1_1") (pintype "passive"))
      (node (ref "SW1") (pin "1") (pinfunction "1_1") (pintype "passive"))
      (node (ref "SW2") (pin "1") (pinfunction "1_1") (pintype "passive"))
      (node (ref "SW3") (pin "1") (pinfunction "1_1") (pintype "passive"))
      (node (ref "TP2") (pin "TP") (pinfunction "TP_TP") (pintype "input"))
      (node (ref "TP_GND") (pin "TP") (pinfunction "TP_TP") (pintype "input"))
      (node (ref "U$11") (pin "1") (pinfunction "1_1") (pintype "passive"))
      (node (ref "U1") (pin "P$74") (pinfunction "VSS_PAD_P$74") (pintype "bidirectional"))
      (node (ref "U1") (pin "P$75") (pinfunction "VSS_PAD_P$75") (pintype "bidirectional"))
      (node (ref "U1") (pin "P$76") (pinfunction "VSS_PAD_P$76") (pintype "bidirectional"))
      (node (ref "U1") (pin "P$77") (pinfunction "VSS_PAD_P$77") (pintype "bidirectional"))
      (node (ref "U1") (pin "P$78") (pinfunction "VSS_PAD_P$78") (pintype "bidirectional"))
      (node (ref "U1") (pin "P$79") (pinfunction "VSS_PAD_P$79") (pintype "bidirectional"))
      (node (ref "U1") (pin "P$80") (pinfunction "VSS_PAD_P$80") (pintype "bidirectional"))
      (node (ref "U1") (pin "P$81") (pinfunction "VSS_PAD_P$81") (pintype "bidirectional"))
      (node (ref "U1") (pin "P$82") (pinfunction "VSS_PAD_P$82") (pintype "bidirectional"))
      (node (ref "U1") (pin "P$83") (pinfunction "VSS_PAD_P$83") (pintype "bidirectional"))
      (node (ref "U1") (pin "P$84") (pinfunction "VSS_PAD_P$84") (pintype "bidirectional"))
      (node (ref "U1") (pin "P$85") (pinfunction "VSS_PAD_P$85") (pintype "bidirectional"))
      (node (ref "U1") (pin "P$86") (pinfunction "VSS_PAD_P$86") (pintype "bidirectional"))
      (node (ref "U1") (pin "P$87") (pinfunction "VSS_PAD_P$87") (pintype "bidirectional"))
      (node (ref "U1") (pin "P$88") (pinfunction "VSS_PAD_P$88") (pintype "bidirectional"))
      (node (ref "U1") (pin "P$89") (pinfunction "VSS_PAD_P$89") (pintype "bidirectional"))
      (node (ref "U1") (pin "P$90") (pinfunction "VSS_PAD_P$90") (pintype "bidirectional"))
      (node (ref "U1") (pin "P$B7") (pinfunction "VSS_P$B7") (pintype "power_in"))
      (node (ref "U1") (pin "P$F23") (pinfunction "VSS_PA_P$F23") (pintype "bidirectional"))
      (node (ref "U3") (pin "1") (pinfunction "CTG_1") (pintype "power_in"))
      (node (ref "U3") (pin "4") (pinfunction "GND_4") (pintype "power_in"))
      (node (ref "U3") (pin "6") (pinfunction "QSTRT_6") (pintype "input"))
      (node (ref "U3") (pin "9") (pinfunction "EP_9") (pintype "power_in"))
      (node (ref "X1") (pin "2") (pinfunction "2_2") (pintype "passive"))
      (node (ref "X1") (pin "4") (pinfunction "4_4") (pintype "passive"))
    )
    (net (code "16") (name "HAPTIC_EN") (class "Default")
      (node (ref "IC4") (pin "A1") (pinfunction "EN_A1") (pintype "bidirectional"))
      (node (ref "U1") (pin "P$U1") (pinfunction "P0.12_P$U1") (pintype "bidirectional"))
    )
    (net (code "17") (name "IMU_INT1") (class "Default")
      (node (ref "IC3") (pin "5") (pinfunction "INT1_5") (pintype "bidirectional"))
      (node (ref "U1") (pin "P$N1") (pinfunction "P0.08_P$N1") (pintype "bidirectional"))
    )
    (net (code "18") (name "IMU_INT2") (class "Default")
      (node (ref "IC3") (pin "6") (pinfunction "INT2_6") (pintype "bidirectional"))
      (node (ref "U1") (pin "P$P2") (pinfunction "P1.08_P$P2") (pintype "bidirectional"))
    )
    (net (code "19") (name "LX1") (class "Default")
      (node (ref "IC9") (pin "B2") (pinfunction "SW1_1_B2") (pintype "bidirectional"))
      (node (ref "IC9") (pin "B3") (pinfunction "SW1_2_B3") (pintype "bidirectional"))
      (node (ref "L7") (pin "1") (pinfunction "1_1") (pintype "bidirectional"))
    )
    (net (code "20") (name "LX2") (class "Default")
      (node (ref "IC9") (pin "D2") (pinfunction "SW2_1_D2") (pintype "bidirectional"))
      (node (ref "IC9") (pin "D3") (pinfunction "SW2_2_D3") (pintype "bidirectional"))
      (node (ref "L7") (pin "2") (pinfunction "2_2") (pintype "bidirectional"))
    )
    (net (code "21") (name "MOSI") (class "Default")
      (node (ref "J1") (pin "14") (pinfunction "14_14") (pintype "bidirectional"))
      (node (ref "U1") (pin "P$B13") (pinfunction "P0.03/AIN1_P$B13") (pintype "bidirectional"))
    )
    (net (code "22") (name "Net-(ANT1-FEED)") (class "Default")
      (node (ref "ANT1") (pin "1") (pinfunction "FEED_1") (pintype "input"))
      (node (ref "C22") (pin "1") (pinfunction "1_1") (pintype "passive"))
      (node (ref "C4") (pin "1") (pinfunction "1_1") (pintype "passive"))
      (node (ref "U$11") (pin "2") (pinfunction "2_2") (pintype "passive"))
    )
    (net (code "23") (name "Net-(D2-K)") (class "Default")
      (node (ref "C2_EP_DR") (pin "1") (pinfunction "1_1") (pintype "passive"))
      (node (ref "D2") (pin "1") (pinfunction "K_1") (pintype "bidirectional"))
      (node (ref "D4") (pin "2") (pinfunction "A_2") (pintype "bidirectional"))
    )
    (net (code "24") (name "Net-(D5-A)") (class "Default")
      (node (ref "C2_EP_DR") (pin "2") (pinfunction "2_2") (pintype "passive"))
      (node (ref "D5") (pin "2") (pinfunction "A_2") (pintype "bidirectional"))
      (node (ref "L5") (pin "1") (pinfunction "1_1") (pintype "passive"))
      (node (ref "Q3") (pin "3") (pinfunction "D_3") (pintype "bidirectional"))
    )
    (net (code "25") (name "Net-(EPD_C1-Pad2)") (class "Default")
      (node (ref "EPD_C1") (pin "2") (pinfunction "2_2") (pintype "passive"))
      (node (ref "J1") (pin "5") (pinfunction "5_5") (pintype "bidirectional"))
    )
    (net (code "26") (name "Net-(EPD_C2-Pad2)") (class "Default")
      (node (ref "EPD_C2") (pin "2") (pinfunction "2_2") (pintype "passive"))
      (node (ref "J1") (pin "4") (pinfunction "4_4") (pintype "bidirectional"))
    )
    (net (code "27") (name "Net-(EPD_C6-Pad2)") (class "Default")
      (node (ref "EPD_C6") (pin "2") (pinfunction "2_2") (pintype "passive"))
      (node (ref "J1") (pin "17") (pinfunction "17_17") (pintype "bidirectional"))
    )
    (net (code "28") (name "Net-(EPD_C7-Pad2)") (class "Default")
      (node (ref "EPD_C7") (pin "2") (pinfunction "2_2") (pintype "passive"))
      (node (ref "J1") (pin "18") (pinfunction "18_18") (pintype "bidirectional"))
    )
    (net (code "29") (name "Net-(EPD_C8-Pad2)") (class "Default")
      (node (ref "EPD_C8") (pin "2") (pinfunction "2_2") (pintype "passive"))
      (node (ref "J1") (pin "20") (pinfunction "20_20") (pintype "bidirectional"))
    )
    (net (code "30") (name "Net-(EPD_C10-Pad2)") (class "Default")
      (node (ref "EPD_C10") (pin "2") (pinfunction "2_2") (pintype "passive"))
      (node (ref "J1") (pin "22") (pinfunction "22_22") (pintype "bidirectional"))
    )
    (net (code "31") (name "Net-(EPD_C12-Pad2)") (class "Default")
      (node (ref "EPD_C12") (pin "2") (pinfunction "2_2") (pintype "passive"))
      (node (ref "J1") (pin "24") (pinfunction "24_24") (pintype "bidirectional"))
    )
    (net (code "32") (name "Net-(IC1-TS{slash}MR)") (class "Default")
      (node (ref "IC1") (pin "D1") (pinfunction "TS/MR_D1") (pintype "bidirectional"))
      (node (ref "R1") (pin "2") (pinfunction "2_2") (pintype "bidirectional"))
    )
    (net (code "33") (name "Net-(IC3-SDO)") (class "Default")
      (node (ref "IC3") (pin "1") (pinfunction "SDO_1") (pintype "bidirectional"))
      (node (ref "R3") (pin "2") (pinfunction "2_2") (pintype "bidirectional"))
    )
    (net (code "34") (name "Net-(IC4-REG)") (class "Default")
      (node (ref "C32") (pin "2") (pinfunction "2_2") (pintype "passive"))
      (node (ref "IC4") (pin "A2") (pinfunction "REG_A2") (pintype "bidirectional"))
    )
    (net (code "35") (name "Net-(IC9-SCL)") (class "Default")
      (node (ref "IC9") (pin "D1") (pinfunction "SCL_D1") (pintype "bidirectional"))
      (node (ref "R4") (pin "2") (pinfunction "2_2") (pintype "bidirectional"))
    )
    (net (code "36") (name "Net-(IC9-SDA)") (class "Default")
      (node (ref "IC9") (pin "E1") (pinfunction "SDA_E1") (pintype "bidirectional"))
      (node (ref "R2") (pin "2") (pinfunction "2_2") (pintype "bidirectional"))
    )
    (net (code "37") (name "Net-(J4-CC1)") (class "Default")
      (node (ref "J4") (pin "A5") (pinfunction "CC1_A5") (pintype "bidirectional"))
      (node (ref "R1_USB") (pin "2") (pinfunction "2_2") (pintype "bidirectional"))
    )
    (net (code "38") (name "Net-(J4-CC2)") (class "Default")
      (node (ref "J4") (pin "B5") (pinfunction "CC2_B5") (pintype "bidirectional"))
      (node (ref "R2_USB") (pin "1") (pinfunction "1_1") (pintype "bidirectional"))
    )
    (net (code "39") (name "Net-(R1_EP_DR-Pad1)") (class "Default")
      (node (ref "R1_EP_DR") (pin "1") (pinfunction "1_1") (pintype "bidirectional"))
      (node (ref "R_TYPE_SEL") (pin "2") (pinfunction "2_2") (pintype "bidirectional"))
      (node (ref "SJ1") (pin "2") (pinfunction "2_2") (pintype "passive"))
    )
    (net (code "40") (name "Net-(U$2-Pad2)") (class "Default")
      (node (ref "U$2") (pin "2") (pinfunction "2_2") (pintype "passive"))
      (node (ref "U$3") (pin "1") (pinfunction "1_1") (pintype "passive"))
    )
    (net (code "41") (name "Net-(U1-ANT)") (class "Default")
      (node (ref "C3") (pin "1") (pinfunction "1_1") (pintype "passive"))
      (node (ref "U1") (pin "P$H23") (pinfunction "ANT_P$H23") (pintype "bidirectional"))
    )
    (net (code "42") (name "Net-(U1-DCC)") (class "Default")
      (node (ref "U$2") (pin "1") (pinfunction "1_1") (pintype "passive"))
      (node (ref "U1") (pin "P$B3") (pinfunction "DCC_P$B3") (pintype "output"))
    )
    (net (code "43") (name "Net-(U1-DEC1)") (class "Default")
      (node (ref "C5") (pin "1") (pinfunction "1_1") (pintype "passive"))
      (node (ref "U1") (pin "P$C1") (pinfunction "DEC1_P$C1") (pintype "power_in"))
    )
    (net (code "44") (name "Net-(U1-DEC2)") (class "Default")
      (node (ref "C13") (pin "1") (pinfunction "1_1") (pintype "passive"))
      (node (ref "U1") (pin "P$A18") (pinfunction "DEC2_P$A18") (pintype "bidirectional"))
    )
    (net (code "45") (name "Net-(U1-DEC3V3)") (class "Default")
      (node (ref "C20") (pin "1") (pinfunction "1_1") (pintype "passive"))
      (node (ref "U1") (pin "P$AC5") (pinfunction "DEC3V3_P$AC5") (pintype "bidirectional"))
    )
    (net (code "46") (name "Net-(U1-DEC5)") (class "Default")
      (node (ref "C9") (pin "1") (pinfunction "1_1") (pintype "passive"))
      (node (ref "U1") (pin "P$N24") (pinfunction "DEC5_P$N24") (pintype "bidirectional"))
    )
    (net (code "47") (name "Net-(U1-XC1)") (class "Default")
      (node (ref "C1") (pin "1") (pinfunction "1_1") (pintype "passive"))
      (node (ref "U1") (pin "P$B24") (pinfunction "XC1_P$B24") (pintype "input"))
      (node (ref "X1") (pin "1") (pinfunction "1_1") (pintype "passive"))
    )
    (net (code "48") (name "Net-(U1-XC2)") (class "Default")
      (node (ref "C2") (pin "1") (pinfunction "1_1") (pintype "passive"))
      (node (ref "U1") (pin "P$A23") (pinfunction "XC2_P$A23") (pintype "output"))
      (node (ref "X1") (pin "3") (pinfunction "3_3") (pintype "passive"))
    )
    (net (code "49") (name "OUT+") (class "Default")
      (node (ref "IC4") (pin "A3") (pinfunction "OUT+_A3") (pintype "bidirectional"))
      (node (ref "TP_OP") (pin "TP") (pinfunction "TP_TP") (pintype "input"))
    )
    (net (code "50") (name "OUT-") (class "Default")
      (node (ref "IC4") (pin "C3") (pinfunction "OUT-_C3") (pintype "bidirectional"))
      (node (ref "TP_ON") (pin "TP") (pinfunction "TP_TP") (pintype "input"))
    )
    (net (code "51") (name "P0.00{slash}XL1") (class "Default")
      (node (ref "C17") (pin "2") (pinfunction "2_2") (pintype "passive"))
      (node (ref "U$20") (pin "1") (pinfunction "1_1") (pintype "passive"))
      (node (ref "U1") (pin "P$D2") (pinfunction "P0.00/XL1_P$D2") (pintype "bidirectional"))
    )
    (net (code "52") (name "P0.01{slash}XL2") (class "Default")
      (node (ref "C18") (pin "2") (pinfunction "2_2") (pintype "passive"))
      (node (ref "U$20") (pin "2") (pinfunction "2_2") (pintype "passive"))
      (node (ref "U1") (pin "P$F2") (pinfunction "P0.01/XL2_P$F2") (pintype "bidirectional"))
    )
    (net (code "53") (name "P0.04") (class "Default")
      (node (ref "U1") (pin "P$J1") (pinfunction "P0.04/AIN2_P$J1") (pintype "bidirectional"))
    )
    (net (code "54") (name "P0.09") (class "Default")
      (node (ref "U1") (pin "P$L24") (pinfunction "P0.09/NFC1_P$L24") (pintype "bidirectional"))
    )
    (net (code "55") (name "P0.13") (class "Default")
      (node (ref "C30") (pin "2") (pinfunction "2_2") (pintype "passive"))
      (node (ref "R5") (pin "1") (pinfunction "1_1") (pintype "bidirectional"))
      (node (ref "SW1") (pin "2") (pinfunction "2_2") (pintype "passive"))
      (node (ref "U1") (pin "P$AD8") (pinfunction "P0.13_P$AD8") (pintype "bidirectional"))
    )
    (net (code "56") (name "P0.14") (class "Default")
      (node (ref "C31") (pin "2") (pinfunction "2_2") (pintype "passive"))
      (node (ref "R8") (pin "1") (pinfunction "1_1") (pintype "bidirectional"))
      (node (ref "SW2") (pin "2") (pinfunction "2_2") (pintype "passive"))
      (node (ref "U1") (pin "P$AC9") (pinfunction "P0.14_P$AC9") (pintype "bidirectional"))
    )
    (net (code "57") (name "P0.19") (class "Default")
      (node (ref "U1") (pin "P$AC15") (pinfunction "P0.19_P$AC15") (pintype "bidirectional"))
    )
    (net (code "58") (name "P0.20") (class "Default")
      (node (ref "U1") (pin "P$AD16") (pinfunction "P0.20_P$AD16") (pintype "bidirectional"))
    )
    (net (code "59") (name "P0.21") (class "Default")
      (node (ref "U1") (pin "P$AC17") (pinfunction "P0.21_P$AC17") (pintype "bidirectional"))
    )
    (net (code "60") (name "P0.23") (class "Default")
      (node (ref "U1") (pin "P$AC19") (pinfunction "P0.23_P$AC19") (pintype "bidirectional"))
    )
    (net (code "61") (name "P0.24") (class "Default")
      (node (ref "U1") (pin "P$AD20") (pinfunction "P0.24_P$AD20") (pintype "bidirectional"))
    )
    (net (code "62") (name "P0.25") (class "Default")
      (node (ref "U1") (pin "P$AC21") (pinfunction "P0.25_P$AC21") (pintype "bidirectional"))
    )
    (net (code "63") (name "P0.26") (class "Default")
      (node (ref "U1") (pin "P$G1") (pinfunction "P0.26_P$G1") (pintype "bidirectional"))
    )
    (net (code "64") (name "P0.27") (class "Default")
      (node (ref "U1") (pin "P$H2") (pinfunction "P0.27_P$H2") (pintype "bidirectional"))
    )
    (net (code "65") (name "P0.28") (class "Default")
      (node (ref "U1") (pin "P$B11") (pinfunction "P0.28/AIN4_P$B11") (pintype "bidirectional"))
    )
    (net (code "66") (name "P0.29") (class "Default")
      (node (ref "U1") (pin "P$A10") (pinfunction "P0.29/AIN5_P$A10") (pintype "bidirectional"))
    )
    (net (code "67") (name "P0.30") (class "Default")
      (node (ref "U1") (pin "P$B9") (pinfunction "P0.30/AIN6_P$B9") (pintype "bidirectional"))
    )
    (net (code "68") (name "P0.31") (class "Default")
      (node (ref "U1") (pin "P$A8") (pinfunction "P0.31/AIN7_P$A8") (pintype "bidirectional"))
    )
    (net (code "69") (name "P1.01") (class "Default")
      (node (ref "Q1") (pin "1") (pinfunction "G_1") (pintype "bidirectional"))
      (node (ref "R_PWR_EPD") (pin "1") (pinfunction "1_1") (pintype "bidirectional"))
      (node (ref "U1") (pin "P$Y23") (pinfunction "P1.01_P$Y23") (pintype "bidirectional"))
    )
    (net (code "70") (name "P1.02") (class "Default")
      (node (ref "C29") (pin "2") (pinfunction "2_2") (pintype "passive"))
      (node (ref "R7") (pin "1") (pinfunction "1_1") (pintype "bidirectional"))
      (node (ref "SW3") (pin "2") (pinfunction "2_2") (pintype "passive"))
      (node (ref "U1") (pin "P$W24") (pinfunction "P1.02_P$W24") (pintype "bidirectional"))
    )
    (net (code "71") (name "P1.03") (class "Default")
      (node (ref "U1") (pin "P$V23") (pinfunction "P1.03_P$V23") (pintype "bidirectional"))
    )
    (net (code "72") (name "P1.04") (class "Default")
      (node (ref "U1") (pin "P$U24") (pinfunction "P1.04_P$U24") (pintype "bidirectional"))
    )
    (net (code "73") (name "P1.05") (class "Default")
      (node (ref "U1") (pin "P$T23") (pinfunction "P1.05_P$T23") (pintype "bidirectional"))
    )
    (net (code "74") (name "P1.06") (class "Default")
      (node (ref "U1") (pin "P$R24") (pinfunction "P1.06_P$R24") (pintype "bidirectional"))
    )
    (net (code "75") (name "P1.07") (class "Default")
      (node (ref "U1") (pin "P$P23") (pinfunction "P1.07_P$P23") (pintype "bidirectional"))
    )
    (net (code "76") (name "P1.09") (class "Default")
      (node (ref "U1") (pin "P$R1") (pinfunction "P1.09_P$R1") (pintype "bidirectional"))
    )
    (net (code "77") (name "P1.10") (class "Default")
      (node (ref "U1") (pin "P$A20") (pinfunction "P1.10_P$A20") (pintype "bidirectional"))
    )
    (net (code "78") (name "P1.11") (class "Default")
      (node (ref "U1") (pin "P$B19") (pinfunction "P1.11_P$B19") (pintype "bidirectional"))
    )
    (net (code "79") (name "P1.12") (class "Default")
      (node (ref "U1") (pin "P$B17") (pinfunction "P1.12_P$B17") (pintype "bidirectional"))
    )
    (net (code "80") (name "P1.13") (class "Default")
      (node (ref "U1") (pin "P$A16") (pinfunction "P1.13_P$A16") (pintype "bidirectional"))
    )
    (net (code "81") (name "P1.14") (class "Default")
      (node (ref "U1") (pin "P$B15") (pinfunction "P1.14_P$B15") (pintype "bidirectional"))
    )
    (net (code "82") (name "P1.15") (class "Default")
      (node (ref "U1") (pin "P$A14") (pinfunction "P1.15_P$A14") (pintype "bidirectional"))
    )
    (net (code "83") (name "PMIC_INT") (class "Default")
      (node (ref "IC1") (pin "A1") (pinfunction "~{INT}_A1") (pintype "bidirectional"))
      (node (ref "U1") (pin "P$T2") (pinfunction "P0.11_P$T2") (pintype "bidirectional"))
    )
    (net (code "84") (name "PO.22") (class "Default")
      (node (ref "U1") (pin "P$AD18") (pinfunction "P0.22_P$AD18") (pintype "bidirectional"))
    )
    (net (code "85") (name "PREVGH") (class "Default")
      (node (ref "D5") (pin "1") (pinfunction "K_1") (pintype "bidirectional"))
      (node (ref "EPD_C9") (pin "2") (pinfunction "2_2") (pintype "passive"))
      (node (ref "J1") (pin "21") (pinfunction "21_21") (pintype "bidirectional"))
    )
    (net (code "86") (name "PREVGL") (class "Default")
      (node (ref "D2") (pin "2") (pinfunction "A_2") (pintype "bidirectional"))
      (node (ref "EPD_C11") (pin "2") (pinfunction "2_2") (pintype "passive"))
      (node (ref "J1") (pin "23") (pinfunction "23_23") (pintype "bidirectional"))
    )
    (net (code "87") (name "RESE") (class "Default")
      (node (ref "J1") (pin "3") (pinfunction "3_3") (pintype "bidirectional"))
      (node (ref "Q3") (pin "2") (pinfunction "S_2") (pintype "bidirectional"))
      (node (ref "R1_EP_DR") (pin "2") (pinfunction "2_2") (pintype "bidirectional"))
    )
    (net (code "88") (name "RESET") (class "Default")
      (node (ref "J2") (pin "6") (pinfunction "6_6") (pintype "bidirectional"))
      (node (ref "TP_RESET") (pin "TP") (pinfunction "TP_TP") (pintype "input"))
      (node (ref "U1") (pin "P$AC13") (pinfunction "P0.18/RESET_P$AC13") (pintype "bidirectional"))
    )
    (net (code "89") (name "SCK") (class "Default")
      (node (ref "J1") (pin "13") (pinfunction "13_13") (pintype "bidirectional"))
      (node (ref "U1") (pin "P$A12") (pinfunction "P0.02/AIN0_P$A12") (pintype "bidirectional"))
    )
    (net (code "90") (name "SCL") (class "Default")
      (node (ref "IC3") (pin "12") (pinfunction "SCX_12") (pintype "bidirectional"))
      (node (ref "IC4") (pin "C1") (pinfunction "SCL_C1") (pintype "bidirectional"))
      (node (ref "R17") (pin "2") (pinfunction "2_2") (pintype "bidirectional"))
      (node (ref "R4") (pin "1") (pinfunction "1_1") (pintype "bidirectional"))
      (node (ref "TP_SCL") (pin "TP") (pinfunction "TP_TP") (pintype "input"))
      (node (ref "U1") (pin "P$M2") (pinfunction "P0.07_P$M2") (pintype "bidirectional"))
      (node (ref "U3") (pin "7") (pinfunction "SCL_7") (pintype "input"))
    )
    (net (code "91") (name "SCL{slash}2.4C") (class "Default")
      (node (ref "IC1") (pin "B1") (pinfunction "SCL_B1") (pintype "bidirectional"))
    )
    (net (code "92") (name "SDA") (class "Default")
      (node (ref "IC3") (pin "2") (pinfunction "SDX_2") (pintype "bidirectional"))
      (node (ref "IC4") (pin "B2") (pinfunction "SDA_B2") (pintype "bidirectional"))
      (node (ref "R18") (pin "2") (pinfunction "2_2") (pintype "bidirectional"))
      (node (ref "R2") (pin "1") (pinfunction "1_1") (pintype "bidirectional"))
      (node (ref "TP_SDA") (pin "TP") (pinfunction "TP_TP") (pintype "input"))
      (node (ref "U1") (pin "P$L1") (pinfunction "P0.06_P$L1") (pintype "bidirectional"))
      (node (ref "U3") (pin "8") (pinfunction "SDA_8") (pintype "bidirectional"))
    )
    (net (code "93") (name "SDA{slash}2.4C") (class "Default")
      (node (ref "IC1") (pin "C1") (pinfunction "SDA_C1") (pintype "bidirectional"))
    )
    (net (code "94") (name "SWDCLK") (class "Default")
      (node (ref "J2") (pin "4") (pinfunction "4_4") (pintype "bidirectional"))
      (node (ref "TP_SWDCLK") (pin "TP") (pinfunction "TP_TP") (pintype "input"))
      (node (ref "U1") (pin "P$AA24") (pinfunction "SWDCLK_P$AA24") (pintype "input"))
    )
    (net (code "95") (name "SWDIO") (class "Default")
      (node (ref "J2") (pin "2") (pinfunction "2_2") (pintype "bidirectional"))
      (node (ref "TP_SWDIO") (pin "TP") (pinfunction "TP_TP") (pintype "input"))
      (node (ref "U1") (pin "P$AC24") (pinfunction "SWDIO_P$AC24") (pintype "bidirectional"))
    )
    (net (code "96") (name "SWO") (class "Default")
      (node (ref "TP_SWO") (pin "TP") (pinfunction "TP_TP") (pintype "input"))
      (node (ref "U1") (pin "P$AD22") (pinfunction "P1.00_P$AD22") (pintype "bidirectional"))
    )
    (net (code "97") (name "VBAT") (class "Default")
      (node (ref "C27") (pin "2") (pinfunction "2_2") (pintype "passive"))
      (node (ref "C37") (pin "2") (pinfunction "2_2") (pintype "passive"))
      (node (ref "IC1") (pin "C2") (pinfunction "BAT_C2") (pintype "bidirectional"))
      (node (ref "TP1") (pin "TP") (pinfunction "TP_TP") (pintype "input"))
      (node (ref "U3") (pin "2") (pinfunction "CELL_2") (pintype "power_in"))
      (node (ref "U3") (pin "3") (pinfunction "VDD_3") (pintype "power_in"))
    )
    (net (code "98") (name "VBUS") (class "Default")
      (node (ref "C21") (pin "1") (pinfunction "1_1") (pintype "passive"))
      (node (ref "C42") (pin "1") (pinfunction "1_1") (pintype "passive"))
      (node (ref "C43") (pin "1") (pinfunction "1_1") (pintype "passive"))
      (node (ref "D3") (pin "5") (pinfunction "VBUS_5") (pintype "bidirectional"))
      (node (ref "J4") (pin "A4_B9") (pinfunction "VBUS_A4_B9") (pintype "power_in"))
      (node (ref "J4") (pin "A9_B4") (pinfunction "VBUS_A9_B4") (pintype "power_in"))
      (node (ref "U1") (pin "P$AD2") (pinfunction "VBUS_P$AD2") (pintype "power_in"))
    )
    (net (code "99") (name "VBUS{slash}2.6D") (class "Default")
      (node (ref "C38") (pin "2") (pinfunction "2_2") (pintype "passive"))
      (node (ref "IC1") (pin "A2") (pinfunction "IN_A2") (pintype "bidirectional"))
    )
    (net (code "100") (name "VREG") (class "Default")
      (node (ref "C23") (pin "2") (pinfunction "2_2") (pintype "passive"))
      (node (ref "C24") (pin "2") (pinfunction "2_2") (pintype "passive"))
      (node (ref "C39") (pin "1") (pinfunction "1_1") (pintype "passive"))
      (node (ref "IC1") (pin "B2") (pinfunction "SYS_B2") (pintype "bidirectional"))
      (node (ref "IC9") (pin "A1") (pinfunction "EN_A1") (pintype "bidirectional"))
      (node (ref "IC9") (pin "A2") (pinfunction "VIN_1_A2") (pintype "bidirectional"))
      (node (ref "IC9") (pin "A3") (pinfunction "VIN_2_A3") (pintype "bidirectional"))
      (node (ref "TP_VREG") (pin "TP") (pinfunction "TP_TP") (pintype "input"))
    )
    (net (code "101") (name "unconnected-(ANT1-NC-Pad2)") (class "Default")
      (node (ref "ANT1") (pin "2") (pinfunction "NC_2") (pintype "no_connect"))
    )
    (net (code "102") (name "unconnected-(IC3-ASCL-Pad11)") (class "Default")
      (node (ref "IC3") (pin "11") (pinfunction "ASCL_11") (pintype "bidirectional"))
    )
    (net (code "103") (name "unconnected-(IC3-ASDA-Pad4)") (class "Default")
      (node (ref "IC3") (pin "4") (pinfunction "ASDA_4") (pintype "bidirectional"))
    )
    (net (code "104") (name "unconnected-(J1-Pad1)") (class "Default")
      (node (ref "J1") (pin "1") (pinfunction "1_1") (pintype "bidirectional"))
    )
    (net (code "105") (name "unconnected-(J1-Pad6)") (class "Default")
      (node (ref "J1") (pin "6") (pinfunction "6_6") (pintype "bidirectional"))
    )
    (net (code "106") (name "unconnected-(J1-Pad7)") (class "Default")
      (node (ref "J1") (pin "7") (pinfunction "7_7") (pintype "bidirectional"))
    )
    (net (code "107") (name "unconnected-(J4-SBU1-PadA8)") (class "Default")
      (node (ref "J4") (pin "A8") (pinfunction "SBU1_A8") (pintype "bidirectional"))
    )
    (net (code "108") (name "unconnected-(J4-SBU2-PadB8)") (class "Default")
      (node (ref "J4") (pin "B8") (pinfunction "SBU2_B8") (pintype "bidirectional"))
    )
    (net (code "109") (name "unconnected-(U1-DCCH-PadP$AB2)") (class "Default")
      (node (ref "U1") (pin "P$AB2") (pinfunction "DCCH_P$AB2") (pintype "bidirectional"))
    )
  )
)
